# FPGA_Banks2.net
KiCad netlist of a schematic drawn in Altium Designer
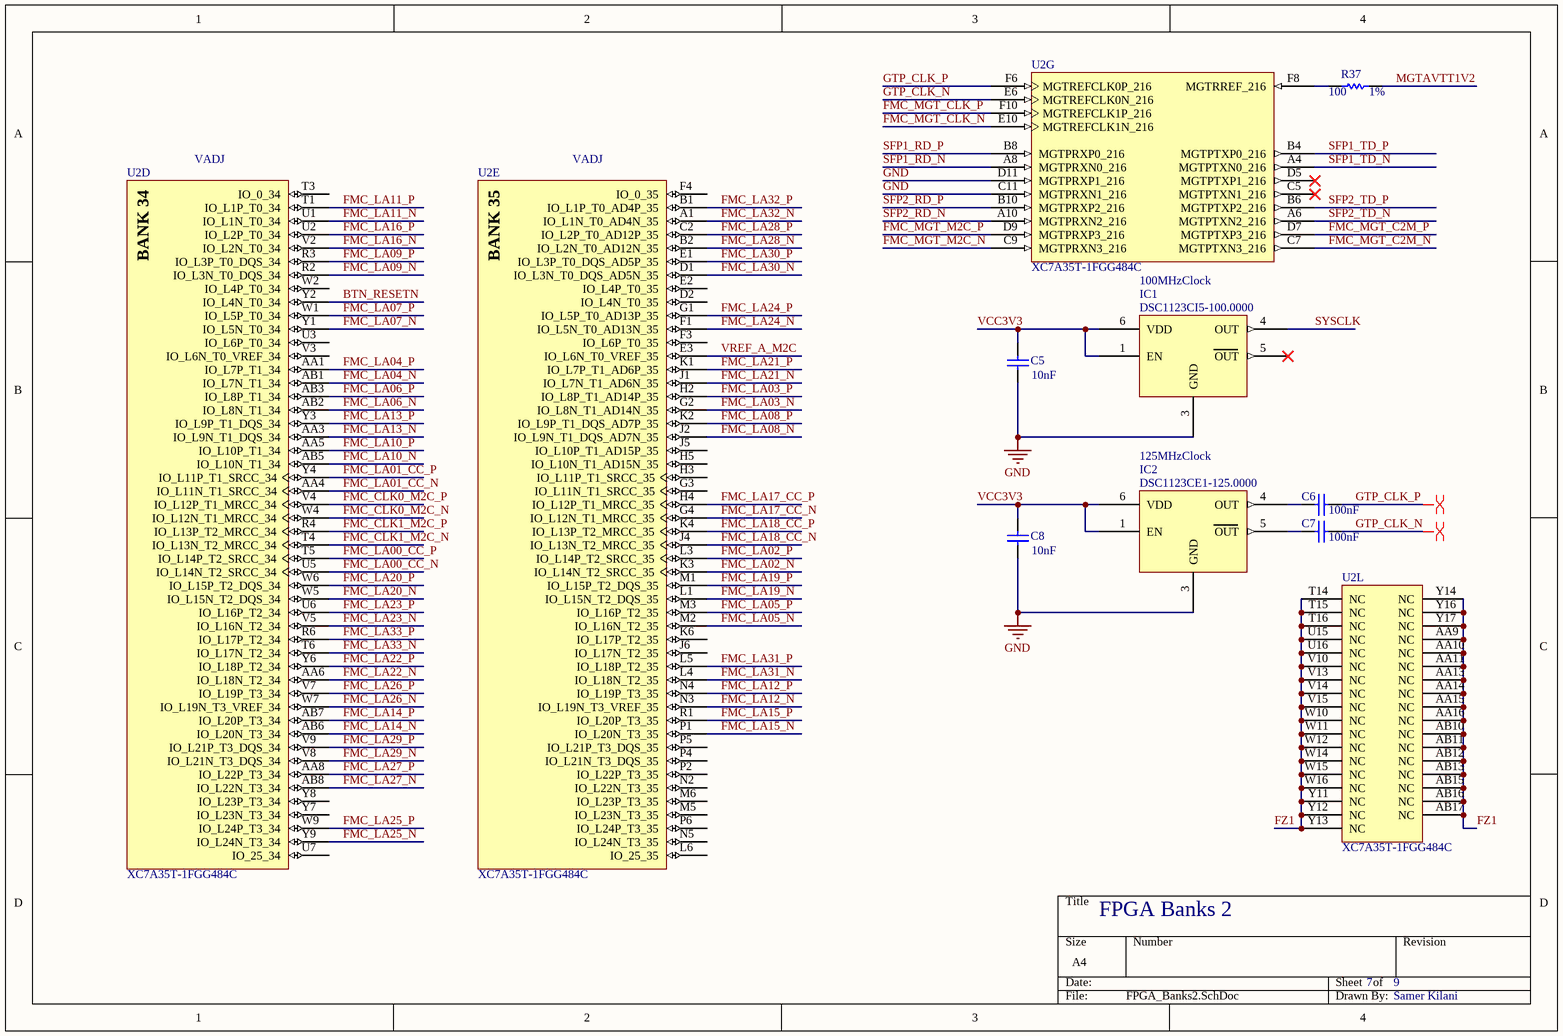
[diagram p0: FPGA_Banks2.SchDoc]

(export (version "E")
  (design (tool "Eeschema 10.0.6"))
  (components
    (comp (ref "C5")
      (value "10nF")
      (footprint "C0402")
      (description "Capacitor")
      (fields (field (name "Comment") "Cap") (field (name "PUBLISHER") "Altium Limited"))
      (libsource (lib "atfclib") (part "Cap"))
    )
    (comp (ref "C6")
      (value "100nF")
      (footprint "C0402")
      (description "Capacitor")
      (fields (field (name "Comment") "Cap") (field (name "PUBLISHER") "Altium Limited"))
      (libsource (lib "atfclib") (part "Cap"))
    )
    (comp (ref "C7")
      (value "100nF")
      (footprint "C0402")
      (description "Capacitor")
      (fields (field (name "Comment") "Cap") (field (name "PUBLISHER") "Altium Limited"))
      (libsource (lib "atfclib") (part "Cap"))
    )
    (comp (ref "C8")
      (value "10nF")
      (footprint "C0402")
      (description "Capacitor")
      (fields (field (name "Comment") "Cap") (field (name "PUBLISHER") "Altium Limited"))
      (libsource (lib "atfclib") (part "Cap"))
    )
    (comp (ref "IC1")
      (value "DSC1123CI5-100.0000")
      (footprint "DSC1123_32_25")
      (description "Standard Clock Oscillators Oscillator Hi Perf -20C-70C 50ppm")
      (libsource (lib "atfclib") (part "DSC1123"))
    )
    (comp (ref "IC2")
      (value "DSC1123CE1-125.0000")
      (footprint "DSC1123_32_25")
      (description "Standard Clock Oscillators Oscillator Hi Perf -20C-70C 50ppm")
      (libsource (lib "atfclib") (part "DSC1123"))
    )
    (comp (ref "R37")
      (value "100")
      (footprint "R0402")
      (description "Resistor")
      (fields (field (name "TOLERANCE") "1%") (field (name "Comment") "Res"))
      (libsource (lib "atfclib") (part "Res"))
    )
    (comp (ref "U2")
      (value "XC7A35T-1FGG484C")
      (footprint "FGG484")
      (description "Artix-7 FPGA, 250 User I/Os, 4 GTP, 484-Ball BGA, Speed Grade 1, Commercial Grade, Pb-Free")
      (fields (field (name "MANUFACTURER") "Xilinx"))
      (libsource (lib "atfclib") (part "XC7A35T-1FGG484C"))
    )
  )
  (nets
    (net (code "1") (name "/BTN_RESETN") (class "Default")
      (node (ref "U2") (pin "Y2") (pinfunction "IO_L4N_T0_34_Y2") (pintype "bidirectional"))
    )
    (net (code "2") (name "/FMC_CLK0_M2C_N") (class "Default")
      (node (ref "U2") (pin "W4") (pinfunction "IO_L12N_T1_MRCC_34_W4") (pintype "bidirectional"))
    )
    (net (code "3") (name "/FMC_CLK0_M2C_P") (class "Default")
      (node (ref "U2") (pin "V4") (pinfunction "IO_L12P_T1_MRCC_34_V4") (pintype "bidirectional"))
    )
    (net (code "4") (name "/FMC_CLK1_M2C_N") (class "Default")
      (node (ref "U2") (pin "T4") (pinfunction "IO_L13N_T2_MRCC_34_T4") (pintype "bidirectional"))
    )
    (net (code "5") (name "/FMC_CLK1_M2C_P") (class "Default")
      (node (ref "U2") (pin "R4") (pinfunction "IO_L13P_T2_MRCC_34_R4") (pintype "bidirectional"))
    )
    (net (code "6") (name "/FMC_LA00_CC_N") (class "Default")
      (node (ref "U2") (pin "U5") (pinfunction "IO_L14N_T2_SRCC_34_U5") (pintype "bidirectional"))
    )
    (net (code "7") (name "/FMC_LA00_CC_P") (class "Default")
      (node (ref "U2") (pin "T5") (pinfunction "IO_L14P_T2_SRCC_34_T5") (pintype "bidirectional"))
    )
    (net (code "8") (name "/FMC_LA01_CC_N") (class "Default")
      (node (ref "U2") (pin "AA4") (pinfunction "IO_L11N_T1_SRCC_34_AA4") (pintype "bidirectional"))
    )
    (net (code "9") (name "/FMC_LA01_CC_P") (class "Default")
      (node (ref "U2") (pin "Y4") (pinfunction "IO_L11P_T1_SRCC_34_Y4") (pintype "bidirectional"))
    )
    (net (code "10") (name "/FMC_LA02_N") (class "Default")
      (node (ref "U2") (pin "K3") (pinfunction "IO_L14N_T2_SRCC_35_K3") (pintype "bidirectional"))
    )
    (net (code "11") (name "/FMC_LA02_P") (class "Default")
      (node (ref "U2") (pin "L3") (pinfunction "IO_L14P_T2_SRCC_35_L3") (pintype "bidirectional"))
    )
    (net (code "12") (name "/FMC_LA03_N") (class "Default")
      (node (ref "U2") (pin "G2") (pinfunction "IO_L8N_T1_AD14N_35_G2") (pintype "bidirectional"))
    )
    (net (code "13") (name "/FMC_LA03_P") (class "Default")
      (node (ref "U2") (pin "H2") (pinfunction "IO_L8P_T1_AD14P_35_H2") (pintype "bidirectional"))
    )
    (net (code "14") (name "/FMC_LA04_N") (class "Default")
      (node (ref "U2") (pin "AB1") (pinfunction "IO_L7N_T1_34_AB1") (pintype "bidirectional"))
    )
    (net (code "15") (name "/FMC_LA04_P") (class "Default")
      (node (ref "U2") (pin "AA1") (pinfunction "IO_L7P_T1_34_AA1") (pintype "bidirectional"))
    )
    (net (code "16") (name "/FMC_LA05_N") (class "Default")
      (node (ref "U2") (pin "M2") (pinfunction "IO_L16N_T2_35_M2") (pintype "bidirectional"))
    )
    (net (code "17") (name "/FMC_LA05_P") (class "Default")
      (node (ref "U2") (pin "M3") (pinfunction "IO_L16P_T2_35_M3") (pintype "bidirectional"))
    )
    (net (code "18") (name "/FMC_LA06_N") (class "Default")
      (node (ref "U2") (pin "AB2") (pinfunction "IO_L8N_T1_34_AB2") (pintype "bidirectional"))
    )
    (net (code "19") (name "/FMC_LA06_P") (class "Default")
      (node (ref "U2") (pin "AB3") (pinfunction "IO_L8P_T1_34_AB3") (pintype "bidirectional"))
    )
    (net (code "20") (name "/FMC_LA07_N") (class "Default")
      (node (ref "U2") (pin "Y1") (pinfunction "IO_L5N_T0_34_Y1") (pintype "bidirectional"))
    )
    (net (code "21") (name "/FMC_LA07_P") (class "Default")
      (node (ref "U2") (pin "W1") (pinfunction "IO_L5P_T0_34_W1") (pintype "bidirectional"))
    )
    (net (code "22") (name "/FMC_LA08_N") (class "Default")
      (node (ref "U2") (pin "J2") (pinfunction "IO_L9N_T1_DQS_AD7N_35_J2") (pintype "bidirectional"))
    )
    (net (code "23") (name "/FMC_LA08_P") (class "Default")
      (node (ref "U2") (pin "K2") (pinfunction "IO_L9P_T1_DQS_AD7P_35_K2") (pintype "bidirectional"))
    )
    (net (code "24") (name "/FMC_LA09_N") (class "Default")
      (node (ref "U2") (pin "R2") (pinfunction "IO_L3N_T0_DQS_34_R2") (pintype "bidirectional"))
    )
    (net (code "25") (name "/FMC_LA09_P") (class "Default")
      (node (ref "U2") (pin "R3") (pinfunction "IO_L3P_T0_DQS_34_R3") (pintype "bidirectional"))
    )
    (net (code "26") (name "/FMC_LA10_N") (class "Default")
      (node (ref "U2") (pin "AB5") (pinfunction "IO_L10N_T1_34_AB5") (pintype "bidirectional"))
    )
    (net (code "27") (name "/FMC_LA10_P") (class "Default")
      (node (ref "U2") (pin "AA5") (pinfunction "IO_L10P_T1_34_AA5") (pintype "bidirectional"))
    )
    (net (code "28") (name "/FMC_LA11_N") (class "Default")
      (node (ref "U2") (pin "U1") (pinfunction "IO_L1N_T0_34_U1") (pintype "bidirectional"))
    )
    (net (code "29") (name "/FMC_LA11_P") (class "Default")
      (node (ref "U2") (pin "T1") (pinfunction "IO_L1P_T0_34_T1") (pintype "bidirectional"))
    )
    (net (code "30") (name "/FMC_LA12_N") (class "Default")
      (node (ref "U2") (pin "N3") (pinfunction "IO_L19N_T3_VREF_35_N3") (pintype "bidirectional"))
    )
    (net (code "31") (name "/FMC_LA12_P") (class "Default")
      (node (ref "U2") (pin "N4") (pinfunction "IO_L19P_T3_35_N4") (pintype "bidirectional"))
    )
    (net (code "32") (name "/FMC_LA13_N") (class "Default")
      (node (ref "U2") (pin "AA3") (pinfunction "IO_L9N_T1_DQS_34_AA3") (pintype "bidirectional"))
    )
    (net (code "33") (name "/FMC_LA13_P") (class "Default")
      (node (ref "U2") (pin "Y3") (pinfunction "IO_L9P_T1_DQS_34_Y3") (pintype "bidirectional"))
    )
    (net (code "34") (name "/FMC_LA14_N") (class "Default")
      (node (ref "U2") (pin "AB6") (pinfunction "IO_L20N_T3_34_AB6") (pintype "bidirectional"))
    )
    (net (code "35") (name "/FMC_LA14_P") (class "Default")
      (node (ref "U2") (pin "AB7") (pinfunction "IO_L20P_T3_34_AB7") (pintype "bidirectional"))
    )
    (net (code "36") (name "/FMC_LA15_N") (class "Default")
      (node (ref "U2") (pin "P1") (pinfunction "IO_L20N_T3_35_P1") (pintype "bidirectional"))
    )
    (net (code "37") (name "/FMC_LA15_P") (class "Default")
      (node (ref "U2") (pin "R1") (pinfunction "IO_L20P_T3_35_R1") (pintype "bidirectional"))
    )
    (net (code "38") (name "/FMC_LA16_N") (class "Default")
      (node (ref "U2") (pin "V2") (pinfunction "IO_L2N_T0_34_V2") (pintype "bidirectional"))
    )
    (net (code "39") (name "/FMC_LA16_P") (class "Default")
      (node (ref "U2") (pin "U2") (pinfunction "IO_L2P_T0_34_U2") (pintype "bidirectional"))
    )
    (net (code "40") (name "/FMC_LA17_CC_N") (class "Default")
      (node (ref "U2") (pin "G4") (pinfunction "IO_L12N_T1_MRCC_35_G4") (pintype "bidirectional"))
    )
    (net (code "41") (name "/FMC_LA17_CC_P") (class "Default")
      (node (ref "U2") (pin "H4") (pinfunction "IO_L12P_T1_MRCC_35_H4") (pintype "bidirectional"))
    )
    (net (code "42") (name "/FMC_LA18_CC_N") (class "Default")
      (node (ref "U2") (pin "J4") (pinfunction "IO_L13N_T2_MRCC_35_J4") (pintype "bidirectional"))
    )
    (net (code "43") (name "/FMC_LA18_CC_P") (class "Default")
      (node (ref "U2") (pin "K4") (pinfunction "IO_L13P_T2_MRCC_35_K4") (pintype "bidirectional"))
    )
    (net (code "44") (name "/FMC_LA19_N") (class "Default")
      (node (ref "U2") (pin "L1") (pinfunction "IO_L15N_T2_DQS_35_L1") (pintype "bidirectional"))
    )
    (net (code "45") (name "/FMC_LA19_P") (class "Default")
      (node (ref "U2") (pin "M1") (pinfunction "IO_L15P_T2_DQS_35_M1") (pintype "bidirectional"))
    )
    (net (code "46") (name "/FMC_LA20_N") (class "Default")
      (node (ref "U2") (pin "W5") (pinfunction "IO_L15N_T2_DQS_34_W5") (pintype "bidirectional"))
    )
    (net (code "47") (name "/FMC_LA20_P") (class "Default")
      (node (ref "U2") (pin "W6") (pinfunction "IO_L15P_T2_DQS_34_W6") (pintype "bidirectional"))
    )
    (net (code "48") (name "/FMC_LA21_N") (class "Default")
      (node (ref "U2") (pin "J1") (pinfunction "IO_L7N_T1_AD6N_35_J1") (pintype "bidirectional"))
    )
    (net (code "49") (name "/FMC_LA21_P") (class "Default")
      (node (ref "U2") (pin "K1") (pinfunction "IO_L7P_T1_AD6P_35_K1") (pintype "bidirectional"))
    )
    (net (code "50") (name "/FMC_LA22_N") (class "Default")
      (node (ref "U2") (pin "AA6") (pinfunction "IO_L18N_T2_34_AA6") (pintype "bidirectional"))
    )
    (net (code "51") (name "/FMC_LA22_P") (class "Default")
      (node (ref "U2") (pin "Y6") (pinfunction "IO_L18P_T2_34_Y6") (pintype "bidirectional"))
    )
    (net (code "52") (name "/FMC_LA23_N") (class "Default")
      (node (ref "U2") (pin "V5") (pinfunction "IO_L16N_T2_34_V5") (pintype "bidirectional"))
    )
    (net (code "53") (name "/FMC_LA23_P") (class "Default")
      (node (ref "U2") (pin "U6") (pinfunction "IO_L16P_T2_34_U6") (pintype "bidirectional"))
    )
    (net (code "54") (name "/FMC_LA24_N") (class "Default")
      (node (ref "U2") (pin "F1") (pinfunction "IO_L5N_T0_AD13N_35_F1") (pintype "bidirectional"))
    )
    (net (code "55") (name "/FMC_LA24_P") (class "Default")
      (node (ref "U2") (pin "G1") (pinfunction "IO_L5P_T0_AD13P_35_G1") (pintype "bidirectional"))
    )
    (net (code "56") (name "/FMC_LA25_N") (class "Default")
      (node (ref "U2") (pin "Y9") (pinfunction "IO_L24N_T3_34_Y9") (pintype "bidirectional"))
    )
    (net (code "57") (name "/FMC_LA25_P") (class "Default")
      (node (ref "U2") (pin "W9") (pinfunction "IO_L24P_T3_34_W9") (pintype "bidirectional"))
    )
    (net (code "58") (name "/FMC_LA26_N") (class "Default")
      (node (ref "U2") (pin "W7") (pinfunction "IO_L19N_T3_VREF_34_W7") (pintype "bidirectional"))
    )
    (net (code "59") (name "/FMC_LA26_P") (class "Default")
      (node (ref "U2") (pin "V7") (pinfunction "IO_L19P_T3_34_V7") (pintype "bidirectional"))
    )
    (net (code "60") (name "/FMC_LA27_N") (class "Default")
      (node (ref "U2") (pin "AB8") (pinfunction "IO_L22N_T3_34_AB8") (pintype "bidirectional"))
    )
    (net (code "61") (name "/FMC_LA27_P") (class "Default")
      (node (ref "U2") (pin "AA8") (pinfunction "IO_L22P_T3_34_AA8") (pintype "bidirectional"))
    )
    (net (code "62") (name "/FMC_LA28_N") (class "Default")
      (node (ref "U2") (pin "B2") (pinfunction "IO_L2N_T0_AD12N_35_B2") (pintype "bidirectional"))
    )
    (net (code "63") (name "/FMC_LA28_P") (class "Default")
      (node (ref "U2") (pin "C2") (pinfunction "IO_L2P_T0_AD12P_35_C2") (pintype "bidirectional"))
    )
    (net (code "64") (name "/FMC_LA29_N") (class "Default")
      (node (ref "U2") (pin "V8") (pinfunction "IO_L21N_T3_DQS_34_V8") (pintype "bidirectional"))
    )
    (net (code "65") (name "/FMC_LA29_P") (class "Default")
      (node (ref "U2") (pin "V9") (pinfunction "IO_L21P_T3_DQS_34_V9") (pintype "bidirectional"))
    )
    (net (code "66") (name "/FMC_LA30_N") (class "Default")
      (node (ref "U2") (pin "D1") (pinfunction "IO_L3N_T0_DQS_AD5N_35_D1") (pintype "bidirectional"))
    )
    (net (code "67") (name "/FMC_LA30_P") (class "Default")
      (node (ref "U2") (pin "E1") (pinfunction "IO_L3P_T0_DQS_AD5P_35_E1") (pintype "bidirectional"))
    )
    (net (code "68") (name "/FMC_LA31_N") (class "Default")
      (node (ref "U2") (pin "L4") (pinfunction "IO_L18N_T2_35_L4") (pintype "bidirectional"))
    )
    (net (code "69") (name "/FMC_LA31_P") (class "Default")
      (node (ref "U2") (pin "L5") (pinfunction "IO_L18P_T2_35_L5") (pintype "bidirectional"))
    )
    (net (code "70") (name "/FMC_LA32_N") (class "Default")
      (node (ref "U2") (pin "A1") (pinfunction "IO_L1N_T0_AD4N_35_A1") (pintype "bidirectional"))
    )
    (net (code "71") (name "/FMC_LA32_P") (class "Default")
      (node (ref "U2") (pin "B1") (pinfunction "IO_L1P_T0_AD4P_35_B1") (pintype "bidirectional"))
    )
    (net (code "72") (name "/FMC_LA33_N") (class "Default")
      (node (ref "U2") (pin "T6") (pinfunction "IO_L17N_T2_34_T6") (pintype "bidirectional"))
    )
    (net (code "73") (name "/FMC_LA33_P") (class "Default")
      (node (ref "U2") (pin "R6") (pinfunction "IO_L17P_T2_34_R6") (pintype "bidirectional"))
    )
    (net (code "74") (name "/FMC_MGT_C2M_N") (class "Default")
      (node (ref "U2") (pin "C7") (pinfunction "MGTPTXN3_216_C7") (pintype "output"))
    )
    (net (code "75") (name "/FMC_MGT_C2M_P") (class "Default")
      (node (ref "U2") (pin "D7") (pinfunction "MGTPTXP3_216_D7") (pintype "output"))
    )
    (net (code "76") (name "/FMC_MGT_CLK_N") (class "Default")
      (node (ref "U2") (pin "E10") (pinfunction "MGTREFCLK1N_216_E10") (pintype "input"))
    )
    (net (code "77") (name "/FMC_MGT_CLK_P") (class "Default")
      (node (ref "U2") (pin "F10") (pinfunction "MGTREFCLK1P_216_F10") (pintype "input"))
    )
    (net (code "78") (name "/FMC_MGT_M2C_N") (class "Default")
      (node (ref "U2") (pin "C9") (pinfunction "MGTPRXN3_216_C9") (pintype "input"))
    )
    (net (code "79") (name "/FMC_MGT_M2C_P") (class "Default")
      (node (ref "U2") (pin "D9") (pinfunction "MGTPRXP3_216_D9") (pintype "input"))
    )
    (net (code "80") (name "/FZ1") (class "Default")
      (node (ref "U2") (pin "AA10") (pinfunction "NC_AA10") (pintype "passive"))
      (node (ref "U2") (pin "AA11") (pinfunction "NC_AA11") (pintype "passive"))
      (node (ref "U2") (pin "AA13") (pinfunction "NC_AA13") (pintype "passive"))
      (node (ref "U2") (pin "AA14") (pinfunction "NC_AA14") (pintype "passive"))
      (node (ref "U2") (pin "AA15") (pinfunction "NC_AA15") (pintype "passive"))
      (node (ref "U2") (pin "AA16") (pinfunction "NC_AA16") (pintype "passive"))
      (node (ref "U2") (pin "AA9") (pinfunction "NC_AA9") (pintype "passive"))
      (node (ref "U2") (pin "AB10") (pinfunction "NC_AB10") (pintype "passive"))
      (node (ref "U2") (pin "AB11") (pinfunction "NC_AB11") (pintype "passive"))
      (node (ref "U2") (pin "AB12") (pinfunction "NC_AB12") (pintype "passive"))
      (node (ref "U2") (pin "AB13") (pinfunction "NC_AB13") (pintype "passive"))
      (node (ref "U2") (pin "AB15") (pinfunction "NC_AB15") (pintype "passive"))
      (node (ref "U2") (pin "AB16") (pinfunction "NC_AB16") (pintype "passive"))
      (node (ref "U2") (pin "AB17") (pinfunction "NC_AB17") (pintype "passive"))
      (node (ref "U2") (pin "T14") (pinfunction "NC_T14") (pintype "passive"))
      (node (ref "U2") (pin "T15") (pinfunction "NC_T15") (pintype "passive"))
      (node (ref "U2") (pin "T16") (pinfunction "NC_T16") (pintype "passive"))
      (node (ref "U2") (pin "U15") (pinfunction "NC_U15") (pintype "passive"))
      (node (ref "U2") (pin "U16") (pinfunction "NC_U16") (pintype "passive"))
      (node (ref "U2") (pin "V10") (pinfunction "NC_V10") (pintype "passive"))
      (node (ref "U2") (pin "V13") (pinfunction "NC_V13") (pintype "passive"))
      (node (ref "U2") (pin "V14") (pinfunction "NC_V14") (pintype "passive"))
      (node (ref "U2") (pin "V15") (pinfunction "NC_V15") (pintype "passive"))
      (node (ref "U2") (pin "W10") (pinfunction "NC_W10") (pintype "passive"))
      (node (ref "U2") (pin "W11") (pinfunction "NC_W11") (pintype "passive"))
      (node (ref "U2") (pin "W12") (pinfunction "NC_W12") (pintype "passive"))
      (node (ref "U2") (pin "W14") (pinfunction "NC_W14") (pintype "passive"))
      (node (ref "U2") (pin "W15") (pinfunction "NC_W15") (pintype "passive"))
      (node (ref "U2") (pin "W16") (pinfunction "NC_W16") (pintype "passive"))
      (node (ref "U2") (pin "Y11") (pinfunction "NC_Y11") (pintype "passive"))
      (node (ref "U2") (pin "Y12") (pinfunction "NC_Y12") (pintype "passive"))
      (node (ref "U2") (pin "Y13") (pinfunction "NC_Y13") (pintype "passive"))
      (node (ref "U2") (pin "Y14") (pinfunction "NC_Y14") (pintype "passive"))
      (node (ref "U2") (pin "Y16") (pinfunction "NC_Y16") (pintype "passive"))
      (node (ref "U2") (pin "Y17") (pinfunction "NC_Y17") (pintype "passive"))
    )
    (net (code "81") (name "/GTP_CLK_N") (class "Default")
      (node (ref "C7") (pin "2") (pinfunction "2_2") (pintype "passive"))
      (node (ref "U2") (pin "E6") (pinfunction "MGTREFCLK0N_216_E6") (pintype "input"))
    )
    (net (code "82") (name "/GTP_CLK_P") (class "Default")
      (node (ref "C6") (pin "2") (pinfunction "2_2") (pintype "passive"))
      (node (ref "U2") (pin "F6") (pinfunction "MGTREFCLK0P_216_F6") (pintype "input"))
    )
    (net (code "83") (name "/MGTAVTT1V2") (class "Default")
      (node (ref "R37") (pin "1") (pinfunction "1_1") (pintype "passive"))
    )
    (net (code "84") (name "/SFP1_RD_N") (class "Default")
      (node (ref "U2") (pin "A8") (pinfunction "MGTPRXN0_216_A8") (pintype "input"))
    )
    (net (code "85") (name "/SFP1_RD_P") (class "Default")
      (node (ref "U2") (pin "B8") (pinfunction "MGTPRXP0_216_B8") (pintype "input"))
    )
    (net (code "86") (name "/SFP1_TD_N") (class "Default")
      (node (ref "U2") (pin "A4") (pinfunction "MGTPTXN0_216_A4") (pintype "output"))
    )
    (net (code "87") (name "/SFP1_TD_P") (class "Default")
      (node (ref "U2") (pin "B4") (pinfunction "MGTPTXP0_216_B4") (pintype "output"))
    )
    (net (code "88") (name "/SFP2_RD_N") (class "Default")
      (node (ref "U2") (pin "A10") (pinfunction "MGTPRXN2_216_A10") (pintype "input"))
    )
    (net (code "89") (name "/SFP2_RD_P") (class "Default")
      (node (ref "U2") (pin "B10") (pinfunction "MGTPRXP2_216_B10") (pintype "input"))
    )
    (net (code "90") (name "/SFP2_TD_N") (class "Default")
      (node (ref "U2") (pin "A6") (pinfunction "MGTPTXN2_216_A6") (pintype "output"))
    )
    (net (code "91") (name "/SFP2_TD_P") (class "Default")
      (node (ref "U2") (pin "B6") (pinfunction "MGTPTXP2_216_B6") (pintype "output"))
    )
    (net (code "92") (name "/SYSCLK") (class "Default")
      (node (ref "IC1") (pin "4") (pinfunction "OUT_4") (pintype "output"))
    )
    (net (code "93") (name "/VCC3V3") (class "Default")
      (node (ref "C5") (pin "2") (pinfunction "2_2") (pintype "passive"))
      (node (ref "C8") (pin "2") (pinfunction "2_2") (pintype "passive"))
      (node (ref "IC1") (pin "1") (pinfunction "EN_1") (pintype "passive"))
      (node (ref "IC1") (pin "6") (pinfunction "VDD_6") (pintype "passive"))
      (node (ref "IC2") (pin "1") (pinfunction "EN_1") (pintype "passive"))
      (node (ref "IC2") (pin "6") (pinfunction "VDD_6") (pintype "passive"))
    )
    (net (code "94") (name "/VREF_A_M2C") (class "Default")
      (node (ref "U2") (pin "E3") (pinfunction "IO_L6N_T0_VREF_35_E3") (pintype "bidirectional"))
    )
    (net (code "95") (name "GND") (class "Default")
      (node (ref "C5") (pin "1") (pinfunction "1_1") (pintype "passive"))
      (node (ref "C8") (pin "1") (pinfunction "1_1") (pintype "passive"))
      (node (ref "IC1") (pin "3") (pinfunction "GND_3") (pintype "passive"))
      (node (ref "IC2") (pin "3") (pinfunction "GND_3") (pintype "passive"))
      (node (ref "U2") (pin "C11") (pinfunction "MGTPRXN1_216_C11") (pintype "input"))
      (node (ref "U2") (pin "D11") (pinfunction "MGTPRXP1_216_D11") (pintype "input"))
    )
    (net (code "96") (name "Net-(C6-Pad1)") (class "Default")
      (node (ref "C6") (pin "1") (pinfunction "1_1") (pintype "passive"))
      (node (ref "IC2") (pin "4") (pinfunction "OUT_4") (pintype "output"))
    )
    (net (code "97") (name "Net-(C7-Pad1)") (class "Default")
      (node (ref "C7") (pin "1") (pinfunction "1_1") (pintype "passive"))
      (node (ref "IC2") (pin "5") (pinfunction "OUT_5") (pintype "output"))
    )
    (net (code "98") (name "Net-(U2G-MGTRREF_216)") (class "Default")
      (node (ref "R37") (pin "2") (pinfunction "2_2") (pintype "passive"))
      (node (ref "U2") (pin "F8") (pinfunction "MGTRREF_216_F8") (pintype "input"))
    )
    (net (code "99") (name "unconnected-(IC1-OUT-Pad5)") (class "Default")
      (node (ref "IC1") (pin "5") (pinfunction "OUT_5") (pintype "output+no_connect"))
    )
    (net (code "100") (name "unconnected-(U2D-IO_0_34-PadT3)") (class "Default")
      (node (ref "U2") (pin "T3") (pinfunction "IO_0_34_T3") (pintype "bidirectional"))
    )
    (net (code "101") (name "unconnected-(U2D-IO_25_34-PadU7)") (class "Default")
      (node (ref "U2") (pin "U7") (pinfunction "IO_25_34_U7") (pintype "bidirectional"))
    )
    (net (code "102") (name "unconnected-(U2D-IO_L4P_T0_34-PadW2)") (class "Default")
      (node (ref "U2") (pin "W2") (pinfunction "IO_L4P_T0_34_W2") (pintype "bidirectional"))
    )
    (net (code "103") (name "unconnected-(U2D-IO_L6N_T0_VREF_34-PadV3)") (class "Default")
      (node (ref "U2") (pin "V3") (pinfunction "IO_L6N_T0_VREF_34_V3") (pintype "bidirectional"))
    )
    (net (code "104") (name "unconnected-(U2D-IO_L6P_T0_34-PadU3)") (class "Default")
      (node (ref "U2") (pin "U3") (pinfunction "IO_L6P_T0_34_U3") (pintype "bidirectional"))
    )
    (net (code "105") (name "unconnected-(U2D-IO_L23N_T3_34-PadY7)") (class "Default")
      (node (ref "U2") (pin "Y7") (pinfunction "IO_L23N_T3_34_Y7") (pintype "bidirectional"))
    )
    (net (code "106") (name "unconnected-(U2D-IO_L23P_T3_34-PadY8)") (class "Default")
      (node (ref "U2") (pin "Y8") (pinfunction "IO_L23P_T3_34_Y8") (pintype "bidirectional"))
    )
    (net (code "107") (name "unconnected-(U2E-IO_0_35-PadF4)") (class "Default")
      (node (ref "U2") (pin "F4") (pinfunction "IO_0_35_F4") (pintype "bidirectional"))
    )
    (net (code "108") (name "unconnected-(U2E-IO_25_35-PadL6)") (class "Default")
      (node (ref "U2") (pin "L6") (pinfunction "IO_25_35_L6") (pintype "bidirectional"))
    )
    (net (code "109") (name "unconnected-(U2E-IO_L4N_T0_35-PadD2)") (class "Default")
      (node (ref "U2") (pin "D2") (pinfunction "IO_L4N_T0_35_D2") (pintype "bidirectional"))
    )
    (net (code "110") (name "unconnected-(U2E-IO_L4P_T0_35-PadE2)") (class "Default")
      (node (ref "U2") (pin "E2") (pinfunction "IO_L4P_T0_35_E2") (pintype "bidirectional"))
    )
    (net (code "111") (name "unconnected-(U2E-IO_L6P_T0_35-PadF3)") (class "Default")
      (node (ref "U2") (pin "F3") (pinfunction "IO_L6P_T0_35_F3") (pintype "bidirectional"))
    )
    (net (code "112") (name "unconnected-(U2E-IO_L10N_T1_AD15N_35-PadH5)") (class "Default")
      (node (ref "U2") (pin "H5") (pinfunction "IO_L10N_T1_AD15N_35_H5") (pintype "bidirectional"))
    )
    (net (code "113") (name "unconnected-(U2E-IO_L10P_T1_AD15P_35-PadJ5)") (class "Default")
      (node (ref "U2") (pin "J5") (pinfunction "IO_L10P_T1_AD15P_35_J5") (pintype "bidirectional"))
    )
    (net (code "114") (name "unconnected-(U2E-IO_L11N_T1_SRCC_35-PadG3)") (class "Default")
      (node (ref "U2") (pin "G3") (pinfunction "IO_L11N_T1_SRCC_35_G3") (pintype "bidirectional"))
    )
    (net (code "115") (name "unconnected-(U2E-IO_L11P_T1_SRCC_35-PadH3)") (class "Default")
      (node (ref "U2") (pin "H3") (pinfunction "IO_L11P_T1_SRCC_35_H3") (pintype "bidirectional"))
    )
    (net (code "116") (name "unconnected-(U2E-IO_L17N_T2_35-PadJ6)") (class "Default")
      (node (ref "U2") (pin "J6") (pinfunction "IO_L17N_T2_35_J6") (pintype "bidirectional"))
    )
    (net (code "117") (name "unconnected-(U2E-IO_L17P_T2_35-PadK6)") (class "Default")
      (node (ref "U2") (pin "K6") (pinfunction "IO_L17P_T2_35_K6") (pintype "bidirectional"))
    )
    (net (code "118") (name "unconnected-(U2E-IO_L21N_T3_DQS_35-PadP4)") (class "Default")
      (node (ref "U2") (pin "P4") (pinfunction "IO_L21N_T3_DQS_35_P4") (pintype "bidirectional"))
    )
    (net (code "119") (name "unconnected-(U2E-IO_L21P_T3_DQS_35-PadP5)") (class "Default")
      (node (ref "U2") (pin "P5") (pinfunction "IO_L21P_T3_DQS_35_P5") (pintype "bidirectional"))
    )
    (net (code "120") (name "unconnected-(U2E-IO_L22N_T3_35-PadN2)") (class "Default")
      (node (ref "U2") (pin "N2") (pinfunction "IO_L22N_T3_35_N2") (pintype "bidirectional"))
    )
    (net (code "121") (name "unconnected-(U2E-IO_L22P_T3_35-PadP2)") (class "Default")
      (node (ref "U2") (pin "P2") (pinfunction "IO_L22P_T3_35_P2") (pintype "bidirectional"))
    )
    (net (code "122") (name "unconnected-(U2E-IO_L23N_T3_35-PadM5)") (class "Default")
      (node (ref "U2") (pin "M5") (pinfunction "IO_L23N_T3_35_M5") (pintype "bidirectional"))
    )
    (net (code "123") (name "unconnected-(U2E-IO_L23P_T3_35-PadM6)") (class "Default")
      (node (ref "U2") (pin "M6") (pinfunction "IO_L23P_T3_35_M6") (pintype "bidirectional"))
    )
    (net (code "124") (name "unconnected-(U2E-IO_L24N_T3_35-PadN5)") (class "Default")
      (node (ref "U2") (pin "N5") (pinfunction "IO_L24N_T3_35_N5") (pintype "bidirectional"))
    )
    (net (code "125") (name "unconnected-(U2E-IO_L24P_T3_35-PadP6)") (class "Default")
      (node (ref "U2") (pin "P6") (pinfunction "IO_L24P_T3_35_P6") (pintype "bidirectional"))
    )
    (net (code "126") (name "unconnected-(U2G-MGTPTXN1_216-PadC5)") (class "Default")
      (node (ref "U2") (pin "C5") (pinfunction "MGTPTXN1_216_C5") (pintype "output+no_connect"))
    )
    (net (code "127") (name "unconnected-(U2G-MGTPTXP1_216-PadD5)") (class "Default")
      (node (ref "U2") (pin "D5") (pinfunction "MGTPTXP1_216_D5") (pintype "output+no_connect"))
    )
  )
)
